# MCU.net
KiCad netlist of a schematic drawn in Altium Designer
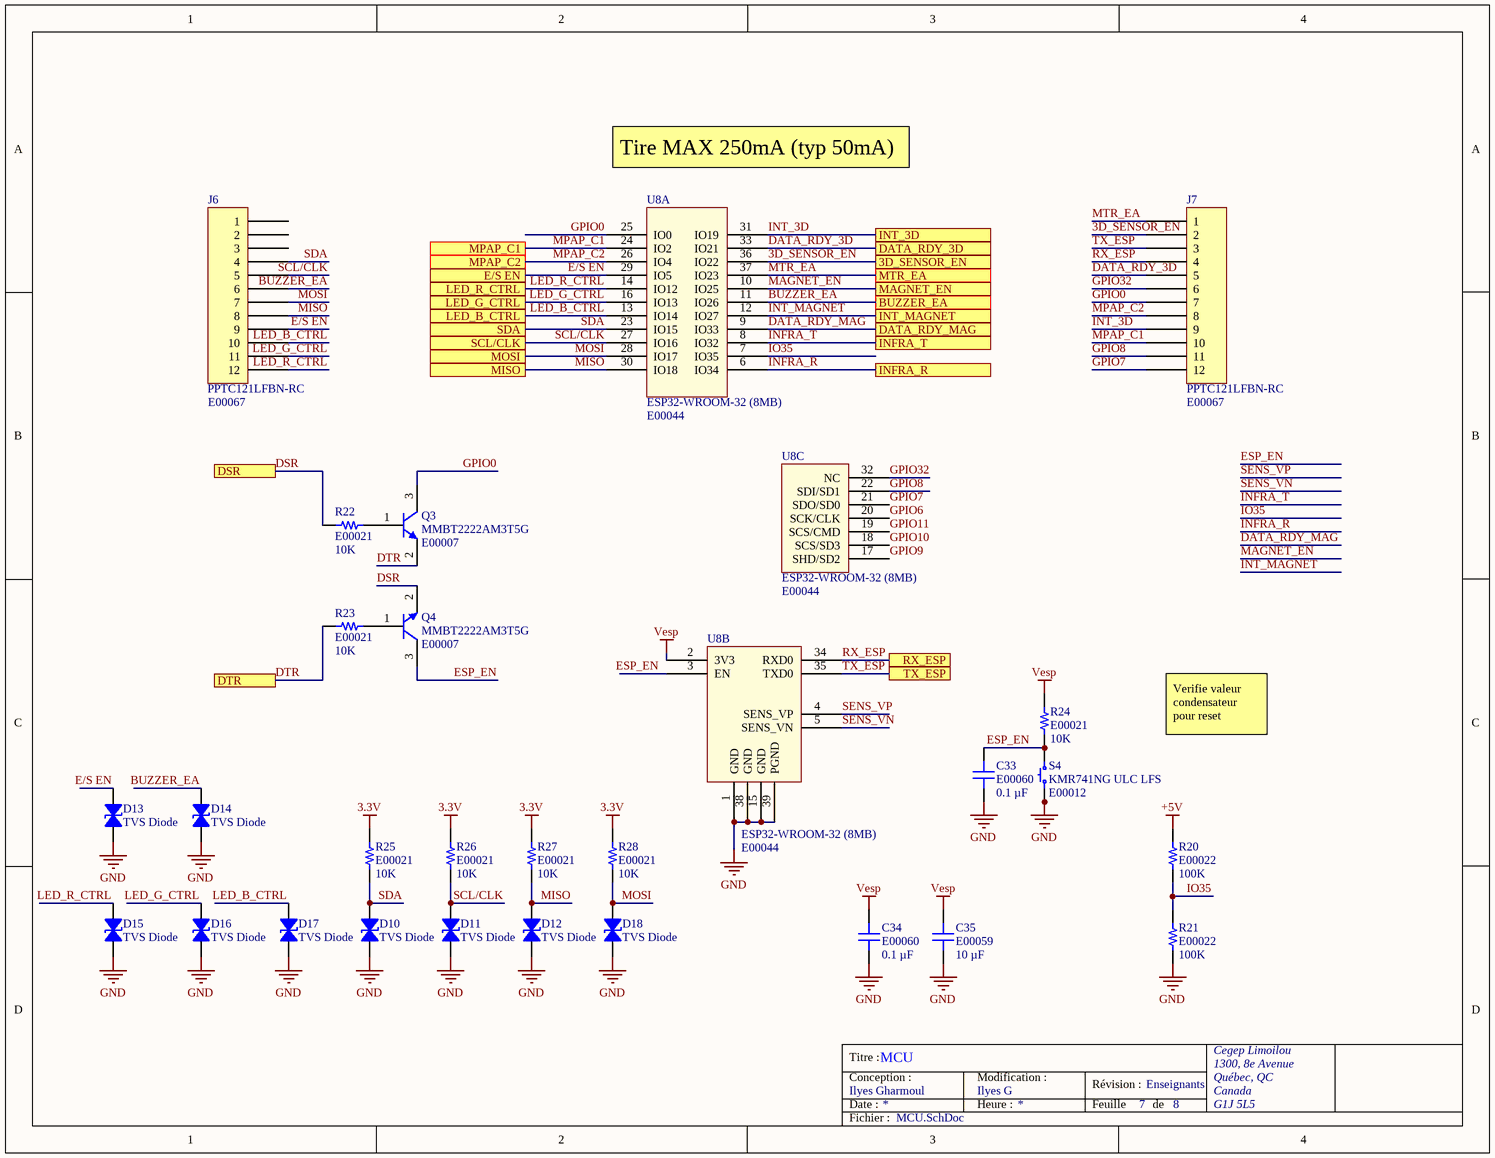
[diagram p0: MCU.SchDoc]

(export (version "E")
  (design (tool "Eeschema 10.0.6"))
  (components
    (comp (ref "C33")
      (value "0.1 µF")
      (footprint "CAP 0603")
      (description "CAP CER 0.1UF 50V X7R 0603")
      (fields
        (field (name "MANUFACTURER") "KEMET")
        (field (name "TOLERANCE") "±10%")
        (field (name "ADAM INVENTORY NUMBER 1") "E00060")
      )
      (libsource (lib "ADAM LIBRARY") (part "CAP CER 0.1UF 50V X7R 0603"))
    )
    (comp (ref "C34")
      (value "0.1 µF")
      (footprint "CAP 0603")
      (description "CAP CER 0.1UF 50V X7R 0603")
      (fields
        (field (name "MANUFACTURER") "KEMET")
        (field (name "TOLERANCE") "±10%")
        (field (name "ADAM INVENTORY NUMBER 1") "E00060")
      )
      (libsource (lib "ADAM LIBRARY") (part "CAP CER 0.1UF 50V X7R 0603"))
    )
    (comp (ref "C35")
      (value "10 µF")
      (footprint "CAP 0603")
      (description "CAP CER 10UF 6.3V X5R 0603")
      (fields
        (field (name "MANUFACTURER") "Murata Electronics")
        (field (name "TOLERANCE") "±20%")
        (field (name "ADAM INVENTORY NUMBER 1") "E00059")
      )
      (libsource (lib "ADAM LIBRARY") (part "CAP CER 10UF 6.3V"))
    )
    (comp (ref "D10")
      (value "TVS Diode")
      (footprint "TVS DIODE")
      (description "TVS DIODE 30.8V 49.9V DO214AC")
      (fields (field (name "MANUFACTURER") "Taiwan Semiconductor Corporation"))
      (libsource (lib "DPIAT202303_DOOR") (part "TVS Diode"))
    )
    (comp (ref "D11")
      (value "TVS Diode")
      (footprint "TVS DIODE")
      (description "TVS DIODE 30.8V 49.9V DO214AC")
      (fields (field (name "MANUFACTURER") "Taiwan Semiconductor Corporation"))
      (libsource (lib "DPIAT202303_DOOR") (part "TVS Diode"))
    )
    (comp (ref "D12")
      (value "TVS Diode")
      (footprint "TVS DIODE")
      (description "TVS DIODE 30.8V 49.9V DO214AC")
      (fields (field (name "MANUFACTURER") "Taiwan Semiconductor Corporation"))
      (libsource (lib "DPIAT202303_DOOR") (part "TVS Diode"))
    )
    (comp (ref "D13")
      (value "TVS Diode")
      (footprint "TVS DIODE")
      (description "TVS DIODE 30.8V 49.9V DO214AC")
      (fields (field (name "MANUFACTURER") "Taiwan Semiconductor Corporation"))
      (libsource (lib "ADAM LIBRARY") (part "TVS Diode"))
    )
    (comp (ref "D14")
      (value "TVS Diode")
      (footprint "TVS DIODE")
      (description "TVS DIODE 30.8V 49.9V DO214AC")
      (fields (field (name "MANUFACTURER") "Taiwan Semiconductor Corporation"))
      (libsource (lib "ADAM LIBRARY") (part "TVS Diode"))
    )
    (comp (ref "D15")
      (value "TVS Diode")
      (footprint "TVS DIODE")
      (description "TVS DIODE 30.8V 49.9V DO214AC")
      (fields (field (name "MANUFACTURER") "Taiwan Semiconductor Corporation"))
      (libsource (lib "ADAM LIBRARY") (part "TVS Diode"))
    )
    (comp (ref "D16")
      (value "TVS Diode")
      (footprint "TVS DIODE")
      (description "TVS DIODE 30.8V 49.9V DO214AC")
      (fields (field (name "MANUFACTURER") "Taiwan Semiconductor Corporation"))
      (libsource (lib "ADAM LIBRARY") (part "TVS Diode"))
    )
    (comp (ref "D17")
      (value "TVS Diode")
      (footprint "TVS DIODE")
      (description "TVS DIODE 30.8V 49.9V DO214AC")
      (fields (field (name "MANUFACTURER") "Taiwan Semiconductor Corporation"))
      (libsource (lib "ADAM LIBRARY") (part "TVS Diode"))
    )
    (comp (ref "D18")
      (value "TVS Diode")
      (footprint "TVS DIODE")
      (description "TVS DIODE 30.8V 49.9V DO214AC")
      (fields (field (name "MANUFACTURER") "Taiwan Semiconductor Corporation"))
      (libsource (lib "DPIAT202303_DOOR") (part "TVS Diode"))
    )
    (comp (ref "J6")
      (value "PPTC121LFBN-RC")
      (footprint "CONN 12PIN FEMALE")
      (description "CONN RCPT 12POS 0.1 GOLD PCB")
      (fields (field (name "MANUFACTURER") "Harwin Inc.") (field (name "ADAM INVENTORY NUMBER 1") "E00067"))
      (libsource (lib "") (part "12PO FEM HEADER_1"))
    )
    (comp (ref "J7")
      (value "PPTC121LFBN-RC")
      (footprint "CONN 12PIN FEMALE")
      (description "CONN RCPT 12POS 0.1 GOLD PCB")
      (fields (field (name "MANUFACTURER") "Harwin Inc.") (field (name "ADAM INVENTORY NUMBER 1") "E00067"))
      (libsource (lib "ADAM LIBRARY") (part "12PO FEM HEADER"))
    )
    (comp (ref "Q3")
      (value "MMBT2222AM3T5G")
      (footprint "SOT-723")
      (description "TRANS NPN 40V 0.6A SOT-723")
      (fields
        (field (name "MANUFACTURER") "ON Semiconductor")
        (field (name "ADAM INVENTORY NUMBER 1") "E00007")
      )
      (libsource (lib "ADAM LIBRARY") (part "TRANS NPN 40V"))
    )
    (comp (ref "Q4")
      (value "MMBT2222AM3T5G")
      (footprint "SOT-723")
      (description "TRANS NPN 40V 0.6A SOT-723")
      (fields
        (field (name "MANUFACTURER") "ON Semiconductor")
        (field (name "ADAM INVENTORY NUMBER 1") "E00007")
      )
      (libsource (lib "ADAM LIBRARY") (part "TRANS NPN 40V"))
    )
    (comp (ref "R20")
      (value "100K")
      (footprint "RES 0603")
      (description "RES SMD 100K OHM 1% 1/4W 0603")
      (fields
        (field (name "MANUFACTURER") "Vishay Dale")
        (field (name "TOLERANCE") "±1%")
        (field (name "ADAM INVENTORY NUMBER 1") "E00022")
      )
      (libsource (lib "ADAM LIBRARY") (part "RES SMD 100K OHM"))
    )
    (comp (ref "R21")
      (value "100K")
      (footprint "RES 0603")
      (description "RES SMD 100K OHM 1% 1/4W 0603")
      (fields
        (field (name "MANUFACTURER") "Vishay Dale")
        (field (name "TOLERANCE") "±1%")
        (field (name "ADAM INVENTORY NUMBER 1") "E00022")
      )
      (libsource (lib "ADAM LIBRARY") (part "RES SMD 100K OHM"))
    )
    (comp (ref "R22")
      (value "10K")
      (footprint "RES 0603")
      (description "RES SMD 10K OHM 1% 1/10W 0603")
      (fields
        (field (name "MANUFACTURER") "Rohm Semiconductor")
        (field (name "TOLERANCE") "±1%")
        (field (name "ADAM INVENTORY NUMBER 1") "E00021")
      )
      (libsource (lib "ADAM LIBRARY") (part "RES SMD 10K OHM"))
    )
    (comp (ref "R23")
      (value "10K")
      (footprint "RES 0603")
      (description "RES SMD 10K OHM 1% 1/10W 0603")
      (fields
        (field (name "MANUFACTURER") "Rohm Semiconductor")
        (field (name "TOLERANCE") "±1%")
        (field (name "ADAM INVENTORY NUMBER 1") "E00021")
      )
      (libsource (lib "ADAM LIBRARY") (part "RES SMD 10K OHM"))
    )
    (comp (ref "R24")
      (value "10K")
      (footprint "RES 0603")
      (description "RES SMD 10K OHM 1% 1/10W 0603")
      (fields
        (field (name "MANUFACTURER") "Rohm Semiconductor")
        (field (name "TOLERANCE") "±1%")
        (field (name "ADAM INVENTORY NUMBER 1") "E00021")
      )
      (libsource (lib "ADAM LIBRARY") (part "RES SMD 10K OHM"))
    )
    (comp (ref "R25")
      (value "10K")
      (footprint "RES 0603")
      (description "RES SMD 10K OHM 1% 1/10W 0603")
      (fields
        (field (name "MANUFACTURER") "Rohm Semiconductor")
        (field (name "TOLERANCE") "±1%")
        (field (name "ADAM INVENTORY NUMBER 1") "E00021")
      )
      (libsource (lib "ADAM LIBRARY") (part "RES SMD 10K OHM"))
    )
    (comp (ref "R26")
      (value "10K")
      (footprint "RES 0603")
      (description "RES SMD 10K OHM 1% 1/10W 0603")
      (fields
        (field (name "MANUFACTURER") "Rohm Semiconductor")
        (field (name "TOLERANCE") "±1%")
        (field (name "ADAM INVENTORY NUMBER 1") "E00021")
      )
      (libsource (lib "ADAM LIBRARY") (part "RES SMD 10K OHM"))
    )
    (comp (ref "R27")
      (value "10K")
      (footprint "RES 0603")
      (description "RES SMD 10K OHM 1% 1/10W 0603")
      (fields
        (field (name "MANUFACTURER") "Rohm Semiconductor")
        (field (name "TOLERANCE") "±1%")
        (field (name "ADAM INVENTORY NUMBER 1") "E00021")
      )
      (libsource (lib "ADAM LIBRARY") (part "RES SMD 10K OHM"))
    )
    (comp (ref "R28")
      (value "10K")
      (footprint "RES 0603")
      (description "RES SMD 10K OHM 1% 1/10W 0603")
      (fields
        (field (name "MANUFACTURER") "Rohm Semiconductor")
        (field (name "TOLERANCE") "±1%")
        (field (name "ADAM INVENTORY NUMBER 1") "E00021")
      )
      (libsource (lib "ADAM LIBRARY") (part "RES SMD 10K OHM"))
    )
    (comp (ref "S4")
      (value "KMR741NG ULC LFS")
      (footprint "Switch Lin SMD")
      (description "SWITCH TACTILE SPST-NO 50MA 32V")
      (fields (field (name "MANUFACTURER") "C&K") (field (name "ADAM INVENTORY NUMBER 1") "E00012"))
      (libsource (lib "ADAM LIBRARY") (part "Sw Lin"))
    )
    (comp (ref "U8")
      (value "ESP32-WROOM-32 (8MB)")
      (footprint "ESP32-WROOM-32D")
      (description "No Description Available")
      (fields
        (field (name "ADAM INVENTORY NUMBER 1") "E00044")
        (field (name "COPYRIGHT") "Copyright (C) 2023 Ultra Librarian. All rights reserved.")
      )
      (libsource (lib "ADAM LIBRARY") (part "ESP32-WROOM-32 (8MB)"))
    )
  )
  (nets
    (net (code "1") (name "+5V") (class "Default")
      (node (ref "R20") (pin "2") (pinfunction "2_2") (pintype "passive"))
    )
    (net (code "2") (name "/3D_SENSOR_EN") (class "Default")
      (node (ref "J7") (pin "2") (pinfunction "2_2") (pintype "passive"))
      (node (ref "U8") (pin "36") (pinfunction "IO22_36") (pintype "passive"))
    )
    (net (code "3") (name "/BUZZER_EA") (class "Default")
      (node (ref "D14") (pin "2") (pinfunction "2_2") (pintype "passive"))
      (node (ref "J6") (pin "6") (pinfunction "6_6") (pintype "passive"))
      (node (ref "U8") (pin "11") (pinfunction "IO26_11") (pintype "passive"))
    )
    (net (code "4") (name "/DATA_RDY_3D") (class "Default")
      (node (ref "J7") (pin "5") (pinfunction "5_5") (pintype "passive"))
      (node (ref "U8") (pin "33") (pinfunction "IO21_33") (pintype "passive"))
    )
    (net (code "5") (name "/DATA_RDY_MAG") (class "Default")
      (node (ref "U8") (pin "9") (pinfunction "IO33_9") (pintype "passive"))
    )
    (net (code "6") (name "/DSR") (class "Default")
      (node (ref "Q4") (pin "2") (pinfunction "E_2") (pintype "passive"))
      (node (ref "R22") (pin "2") (pinfunction "2_2") (pintype "passive"))
    )
    (net (code "7") (name "/DTR") (class "Default")
      (node (ref "Q3") (pin "2") (pinfunction "E_2") (pintype "passive"))
      (node (ref "R23") (pin "2") (pinfunction "2_2") (pintype "passive"))
    )
    (net (code "8") (name "/ESP_EN") (class "Default")
      (node (ref "C33") (pin "2") (pinfunction "2_2") (pintype "passive"))
      (node (ref "Q4") (pin "3") (pinfunction "C_3") (pintype "passive"))
      (node (ref "R24") (pin "1") (pinfunction "1_1") (pintype "passive"))
      (node (ref "S4") (pin "3") (pinfunction "3_3") (pintype "passive"))
      (node (ref "S4") (pin "4") (pinfunction "4_4") (pintype "passive"))
      (node (ref "U8") (pin "3") (pinfunction "EN_3") (pintype "passive"))
    )
    (net (code "9") (name "/E{slash}S EN") (class "Default")
      (node (ref "D13") (pin "2") (pinfunction "2_2") (pintype "passive"))
      (node (ref "J6") (pin "9") (pinfunction "9_9") (pintype "passive"))
      (node (ref "U8") (pin "29") (pinfunction "IO5_29") (pintype "passive"))
    )
    (net (code "10") (name "/GPIO0") (class "Default")
      (node (ref "J7") (pin "7") (pinfunction "7_7") (pintype "passive"))
      (node (ref "Q3") (pin "3") (pinfunction "C_3") (pintype "passive"))
      (node (ref "U8") (pin "25") (pinfunction "IO0_25") (pintype "passive"))
    )
    (net (code "11") (name "/GPIO6") (class "Default")
      (node (ref "U8") (pin "20") (pinfunction "SCK/CLK_20") (pintype "passive"))
    )
    (net (code "12") (name "/GPIO7") (class "Default")
      (node (ref "J7") (pin "12") (pinfunction "12_12") (pintype "passive"))
      (node (ref "U8") (pin "21") (pinfunction "SDO/SD0_21") (pintype "passive"))
    )
    (net (code "13") (name "/GPIO8") (class "Default")
      (node (ref "J7") (pin "11") (pinfunction "11_11") (pintype "passive"))
      (node (ref "U8") (pin "22") (pinfunction "SDI/SD1_22") (pintype "passive"))
    )
    (net (code "14") (name "/GPIO9") (class "Default")
      (node (ref "U8") (pin "17") (pinfunction "SHD/SD2_17") (pintype "passive"))
    )
    (net (code "15") (name "/GPIO10") (class "Default")
      (node (ref "U8") (pin "18") (pinfunction "SCS/SD3_18") (pintype "passive"))
    )
    (net (code "16") (name "/GPIO11") (class "Default")
      (node (ref "U8") (pin "19") (pinfunction "SCS/CMD_19") (pintype "passive"))
    )
    (net (code "17") (name "/GPIO32") (class "Default")
      (node (ref "J7") (pin "6") (pinfunction "6_6") (pintype "passive"))
      (node (ref "U8") (pin "32") (pinfunction "NC_32") (pintype "passive"))
    )
    (net (code "18") (name "/INFRA_R") (class "Default")
      (node (ref "U8") (pin "6") (pinfunction "IO34_6") (pintype "passive"))
    )
    (net (code "19") (name "/INFRA_T") (class "Default")
      (node (ref "U8") (pin "8") (pinfunction "IO32_8") (pintype "passive"))
    )
    (net (code "20") (name "/INT_3D") (class "Default")
      (node (ref "J7") (pin "9") (pinfunction "9_9") (pintype "passive"))
      (node (ref "U8") (pin "31") (pinfunction "IO19_31") (pintype "passive"))
    )
    (net (code "21") (name "/INT_MAGNET") (class "Default")
      (node (ref "U8") (pin "12") (pinfunction "IO27_12") (pintype "passive"))
    )
    (net (code "22") (name "/IO35") (class "Default")
      (node (ref "R20") (pin "1") (pinfunction "1_1") (pintype "passive"))
      (node (ref "R21") (pin "2") (pinfunction "2_2") (pintype "passive"))
      (node (ref "U8") (pin "7") (pinfunction "IO35_7") (pintype "passive"))
    )
    (net (code "23") (name "/LED_B_CTRL") (class "Default")
      (node (ref "D17") (pin "2") (pinfunction "2_2") (pintype "passive"))
      (node (ref "J6") (pin "10") (pinfunction "10_10") (pintype "passive"))
      (node (ref "U8") (pin "13") (pinfunction "IO14_13") (pintype "passive"))
    )
    (net (code "24") (name "/LED_G_CTRL") (class "Default")
      (node (ref "D16") (pin "2") (pinfunction "2_2") (pintype "passive"))
      (node (ref "J6") (pin "11") (pinfunction "11_11") (pintype "passive"))
      (node (ref "U8") (pin "16") (pinfunction "IO13_16") (pintype "passive"))
    )
    (net (code "25") (name "/LED_R_CTRL") (class "Default")
      (node (ref "D15") (pin "2") (pinfunction "2_2") (pintype "passive"))
      (node (ref "J6") (pin "12") (pinfunction "12_12") (pintype "passive"))
      (node (ref "U8") (pin "14") (pinfunction "IO12_14") (pintype "passive"))
    )
    (net (code "26") (name "/MAGNET_EN") (class "Default")
      (node (ref "U8") (pin "10") (pinfunction "IO25_10") (pintype "passive"))
    )
    (net (code "27") (name "/MISO") (class "Default")
      (node (ref "D12") (pin "2") (pinfunction "2_2") (pintype "passive"))
      (node (ref "J6") (pin "8") (pinfunction "8_8") (pintype "passive"))
      (node (ref "R27") (pin "1") (pinfunction "1_1") (pintype "passive"))
      (node (ref "U8") (pin "30") (pinfunction "IO18_30") (pintype "passive"))
    )
    (net (code "28") (name "/MOSI") (class "Default")
      (node (ref "D18") (pin "2") (pinfunction "2_2") (pintype "passive"))
      (node (ref "J6") (pin "7") (pinfunction "7_7") (pintype "passive"))
      (node (ref "R28") (pin "1") (pinfunction "1_1") (pintype "passive"))
      (node (ref "U8") (pin "28") (pinfunction "IO17_28") (pintype "passive"))
    )
    (net (code "29") (name "/MPAP_C1") (class "Default")
      (node (ref "J7") (pin "10") (pinfunction "10_10") (pintype "passive"))
      (node (ref "U8") (pin "24") (pinfunction "IO2_24") (pintype "passive"))
    )
    (net (code "30") (name "/MPAP_C2") (class "Default")
      (node (ref "J7") (pin "8") (pinfunction "8_8") (pintype "passive"))
      (node (ref "U8") (pin "26") (pinfunction "IO4_26") (pintype "passive"))
    )
    (net (code "31") (name "/MTR_EA") (class "Default")
      (node (ref "J7") (pin "1") (pinfunction "1_1") (pintype "passive"))
      (node (ref "U8") (pin "37") (pinfunction "IO23_37") (pintype "passive"))
    )
    (net (code "32") (name "/RX_ESP") (class "Default")
      (node (ref "J7") (pin "4") (pinfunction "4_4") (pintype "passive"))
      (node (ref "U8") (pin "34") (pinfunction "RXD0_34") (pintype "passive"))
    )
    (net (code "33") (name "/SCL{slash}CLK") (class "Default")
      (node (ref "D11") (pin "2") (pinfunction "2_2") (pintype "passive"))
      (node (ref "J6") (pin "5") (pinfunction "5_5") (pintype "passive"))
      (node (ref "R26") (pin "1") (pinfunction "1_1") (pintype "passive"))
      (node (ref "U8") (pin "27") (pinfunction "IO16_27") (pintype "passive"))
    )
    (net (code "34") (name "/SDA") (class "Default")
      (node (ref "D10") (pin "2") (pinfunction "2_2") (pintype "passive"))
      (node (ref "J6") (pin "4") (pinfunction "4_4") (pintype "passive"))
      (node (ref "R25") (pin "1") (pinfunction "1_1") (pintype "passive"))
      (node (ref "U8") (pin "23") (pinfunction "IO15_23") (pintype "passive"))
    )
    (net (code "35") (name "/SENS_VN") (class "Default")
      (node (ref "U8") (pin "5") (pinfunction "SENS_VN_5") (pintype "passive"))
    )
    (net (code "36") (name "/SENS_VP") (class "Default")
      (node (ref "U8") (pin "4") (pinfunction "SENS_VP_4") (pintype "passive"))
    )
    (net (code "37") (name "/TX_ESP") (class "Default")
      (node (ref "J7") (pin "3") (pinfunction "3_3") (pintype "passive"))
      (node (ref "U8") (pin "35") (pinfunction "TXD0_35") (pintype "passive"))
    )
    (net (code "38") (name "3.3V") (class "Default")
      (node (ref "R25") (pin "2") (pinfunction "2_2") (pintype "passive"))
      (node (ref "R26") (pin "2") (pinfunction "2_2") (pintype "passive"))
      (node (ref "R27") (pin "2") (pinfunction "2_2") (pintype "passive"))
      (node (ref "R28") (pin "2") (pinfunction "2_2") (pintype "passive"))
    )
    (net (code "39") (name "GND") (class "Default")
      (node (ref "C33") (pin "1") (pinfunction "1_1") (pintype "passive"))
      (node (ref "C34") (pin "1") (pinfunction "1_1") (pintype "passive"))
      (node (ref "C35") (pin "1") (pinfunction "1_1") (pintype "passive"))
      (node (ref "D10") (pin "1") (pinfunction "1_1") (pintype "passive"))
      (node (ref "D11") (pin "1") (pinfunction "1_1") (pintype "passive"))
      (node (ref "D12") (pin "1") (pinfunction "1_1") (pintype "passive"))
      (node (ref "D13") (pin "1") (pinfunction "1_1") (pintype "passive"))
      (node (ref "D14") (pin "1") (pinfunction "1_1") (pintype "passive"))
      (node (ref "D15") (pin "1") (pinfunction "1_1") (pintype "passive"))
      (node (ref "D16") (pin "1") (pinfunction "1_1") (pintype "passive"))
      (node (ref "D17") (pin "1") (pinfunction "1_1") (pintype "passive"))
      (node (ref "D18") (pin "1") (pinfunction "1_1") (pintype "passive"))
      (node (ref "R21") (pin "1") (pinfunction "1_1") (pintype "passive"))
      (node (ref "S4") (pin "1") (pinfunction "1_1") (pintype "passive"))
      (node (ref "S4") (pin "2") (pinfunction "2_2") (pintype "passive"))
      (node (ref "U8") (pin "1") (pinfunction "GND_1") (pintype "passive"))
      (node (ref "U8") (pin "15") (pinfunction "GND_15") (pintype "passive"))
      (node (ref "U8") (pin "38") (pinfunction "GND_38") (pintype "passive"))
      (node (ref "U8") (pin "39") (pinfunction "PGND_39") (pintype "passive"))
    )
    (net (code "40") (name "Net-(Q3-B)") (class "Default")
      (node (ref "Q3") (pin "1") (pinfunction "B_1") (pintype "passive"))
      (node (ref "R22") (pin "1") (pinfunction "1_1") (pintype "passive"))
    )
    (net (code "41") (name "Net-(Q4-B)") (class "Default")
      (node (ref "Q4") (pin "1") (pinfunction "B_1") (pintype "passive"))
      (node (ref "R23") (pin "1") (pinfunction "1_1") (pintype "passive"))
    )
    (net (code "42") (name "Vesp") (class "Default")
      (node (ref "C34") (pin "2") (pinfunction "2_2") (pintype "passive"))
      (node (ref "C35") (pin "2") (pinfunction "2_2") (pintype "passive"))
      (node (ref "R24") (pin "2") (pinfunction "2_2") (pintype "passive"))
      (node (ref "U8") (pin "2") (pinfunction "3V3_2") (pintype "passive"))
    )
    (net (code "43") (name "unconnected-(J6-Pad1)") (class "Default")
      (node (ref "J6") (pin "1") (pinfunction "1_1") (pintype "passive"))
    )
    (net (code "44") (name "unconnected-(J6-Pad2)") (class "Default")
      (node (ref "J6") (pin "2") (pinfunction "2_2") (pintype "passive"))
    )
    (net (code "45") (name "unconnected-(J6-Pad3)") (class "Default")
      (node (ref "J6") (pin "3") (pinfunction "3_3") (pintype "passive"))
    )
  )
)
